# schematic.net
KiCad netlist of a schematic drawn in EasyEDA
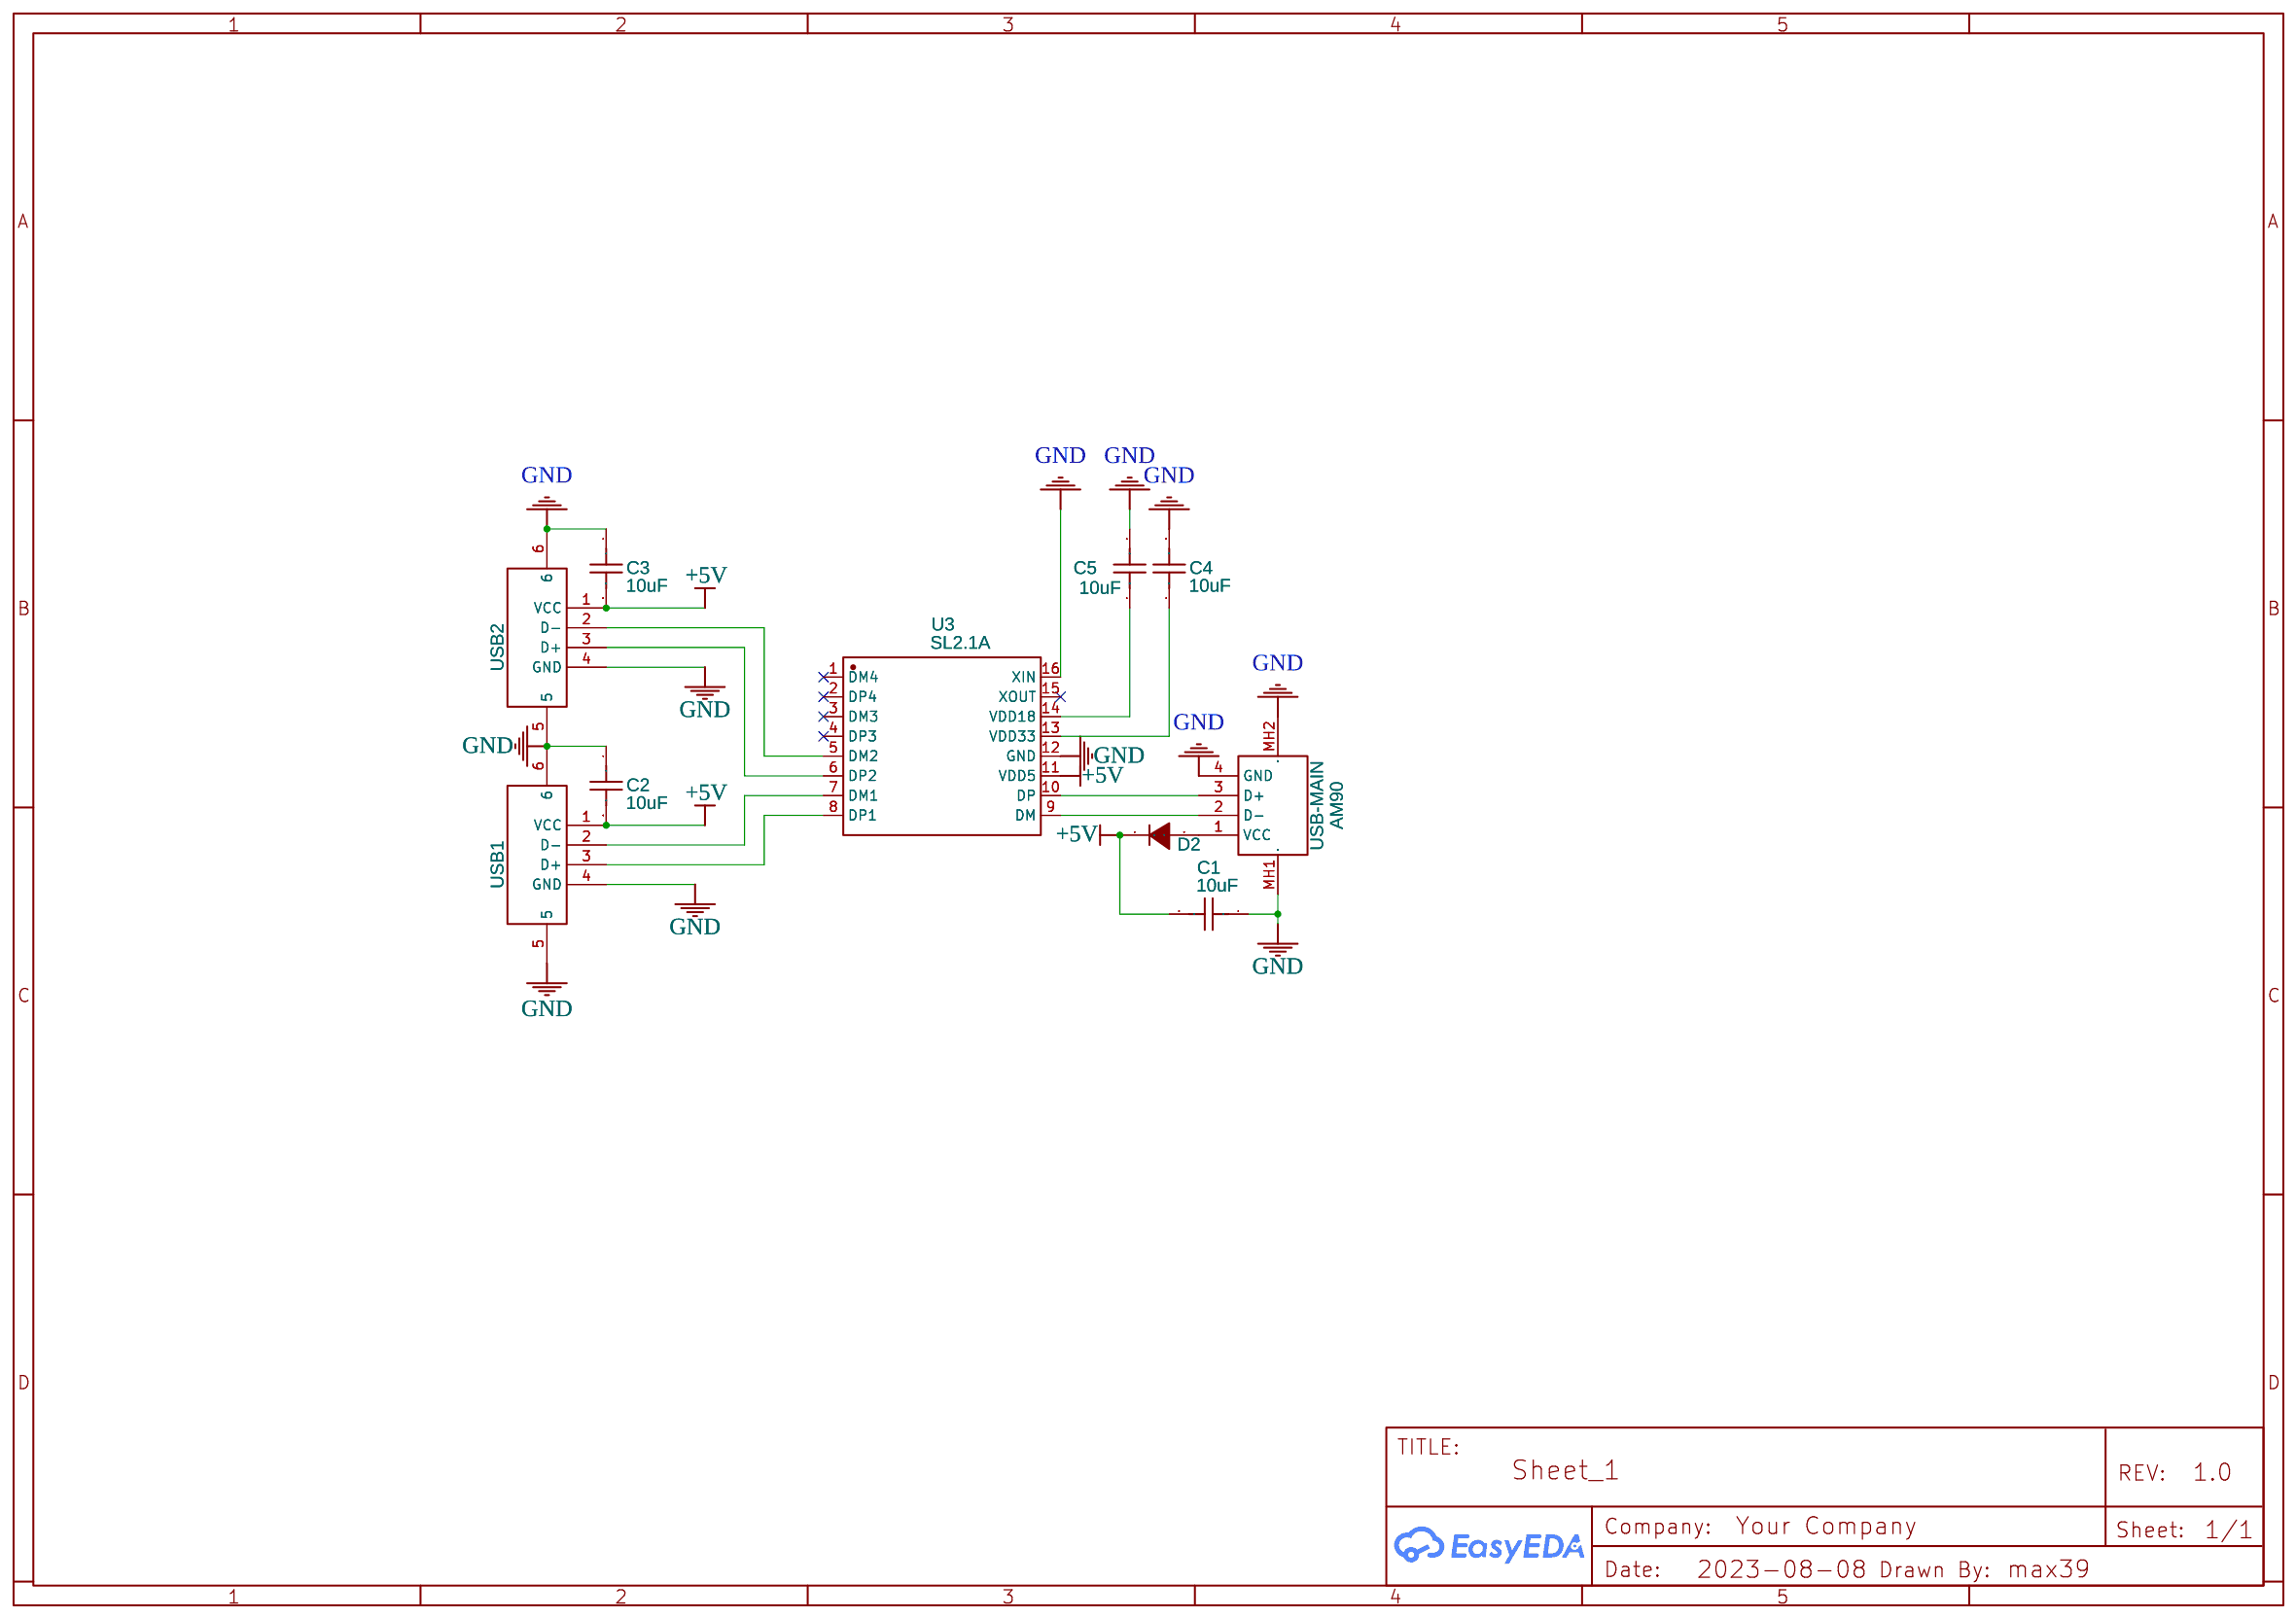
[diagram p0: schematic sheet]

(export (version "E")
  (design (tool "Eeschema 10.0.6"))
  (components
    (comp (ref "C1")
      (value "10uF")
      (fields
        (field (name "Manufacturer Part") "CL10A106KP8NNNC")
        (field (name "Manufacturer") "SAMSUNG(三星)")
      )
      (libsource (lib "") (part "CL10A106KP8NNNC_1"))
    )
    (comp (ref "C2")
      (value "10uF")
      (fields
        (field (name "Manufacturer Part") "CL10A106KP8NNNC")
        (field (name "Manufacturer") "SAMSUNG(三星)")
      )
      (libsource (lib "") (part "CL10A106KP8NNNC"))
    )
    (comp (ref "C3")
      (value "10uF")
      (fields
        (field (name "Manufacturer Part") "CL10A106KP8NNNC")
        (field (name "Manufacturer") "SAMSUNG(三星)")
      )
      (libsource (lib "") (part "CL10A106KP8NNNC"))
    )
    (comp (ref "C4") (value "10uF") (libsource (lib "") (part "C_0603_US")))
    (comp (ref "C5") (value "10uF") (libsource (lib "") (part "C_0603_US")))
    (comp (ref "D2")
      (value "NSR0320MW2T1G")
      (fields (field (name "Manufacturer") "onsemi(安森美)"))
      (libsource (lib "") (part "NSR0320MW2T1G"))
    )
    (comp (ref "U3")
      (value "SL2.1A")
      (fields (field (name "Manufacturer") "CoreChips(和芯润德)"))
      (libsource (lib "") (part "SL2.1A"))
    )
    (comp (ref "USB-MAIN") (value "AM90") (libsource (lib "") (part "AM90")))
    (comp (ref "USB1")
      (value "USB-AF-90-14.4X13.6-H7.0-DIP")
      (fields (field (name "Manufacturer Part") "903-131A1011D10100") (field (name "Manufacturer") "精拓金"))
      (libsource (lib "") (part "USB-AF-90-14.4X13.6-H7.0-DIP"))
    )
    (comp (ref "USB2")
      (value "USB-AF-90-14.4X13.6-H7.0-DIP")
      (fields (field (name "Manufacturer Part") "903-131A1011D10100") (field (name "Manufacturer") "精拓金"))
      (libsource (lib "") (part "USB-AF-90-14.4X13.6-H7.0-DIP"))
    )
  )
  (nets
    (net (code "1") (name "+5V") (class "Default")
      (node (ref "C1") (pin "2") (pinfunction "2_2") (pintype "unspecified"))
      (node (ref "C2") (pin "2") (pinfunction "2_2") (pintype "unspecified"))
      (node (ref "C3") (pin "2") (pinfunction "2_2") (pintype "unspecified"))
      (node (ref "D2") (pin "1") (pinfunction "C_1") (pintype "unspecified"))
      (node (ref "U3") (pin "11") (pinfunction "VDD5_11") (pintype "unspecified"))
      (node (ref "USB1") (pin "1") (pinfunction "VCC_1") (pintype "unspecified"))
      (node (ref "USB2") (pin "1") (pinfunction "VCC_1") (pintype "unspecified"))
    )
    (net (code "2") (name "GND") (class "Default")
      (node (ref "C1") (pin "1") (pinfunction "1_1") (pintype "unspecified"))
      (node (ref "C2") (pin "1") (pinfunction "1_1") (pintype "unspecified"))
      (node (ref "C3") (pin "1") (pinfunction "1_1") (pintype "unspecified"))
      (node (ref "C4") (pin "2") (pinfunction "2_2") (pintype "unspecified"))
      (node (ref "C5") (pin "2") (pinfunction "2_2") (pintype "unspecified"))
      (node (ref "U3") (pin "12") (pinfunction "GND_12") (pintype "unspecified"))
      (node (ref "U3") (pin "16") (pinfunction "XIN_16") (pintype "unspecified"))
      (node (ref "USB-MAIN") (pin "4") (pinfunction "GND_4") (pintype "input"))
      (node (ref "USB-MAIN") (pin "MH1") (pinfunction "MH1_MH1") (pintype "unspecified"))
      (node (ref "USB-MAIN") (pin "MH2") (pinfunction "MH2_MH2") (pintype "unspecified"))
      (node (ref "USB1") (pin "4") (pinfunction "GND_4") (pintype "unspecified"))
      (node (ref "USB1") (pin "5") (pinfunction "5_5") (pintype "unspecified"))
      (node (ref "USB1") (pin "6") (pinfunction "6_6") (pintype "unspecified"))
      (node (ref "USB2") (pin "4") (pinfunction "GND_4") (pintype "unspecified"))
      (node (ref "USB2") (pin "5") (pinfunction "5_5") (pintype "unspecified"))
      (node (ref "USB2") (pin "6") (pinfunction "6_6") (pintype "unspecified"))
    )
    (net (code "3") (name "Net-(D2-A)") (class "Default")
      (node (ref "D2") (pin "2") (pinfunction "A_2") (pintype "unspecified"))
      (node (ref "USB-MAIN") (pin "1") (pinfunction "VCC_1") (pintype "input"))
    )
    (net (code "4") (name "Net-(U3-DM)") (class "Default")
      (node (ref "U3") (pin "9") (pinfunction "DM_9") (pintype "unspecified"))
      (node (ref "USB-MAIN") (pin "2") (pinfunction "D-_2") (pintype "input"))
    )
    (net (code "5") (name "Net-(U3-DM1)") (class "Default")
      (node (ref "U3") (pin "7") (pinfunction "DM1_7") (pintype "unspecified"))
      (node (ref "USB1") (pin "2") (pinfunction "D-_2") (pintype "unspecified"))
    )
    (net (code "6") (name "Net-(U3-DM2)") (class "Default")
      (node (ref "U3") (pin "5") (pinfunction "DM2_5") (pintype "unspecified"))
      (node (ref "USB2") (pin "2") (pinfunction "D-_2") (pintype "unspecified"))
    )
    (net (code "7") (name "Net-(U3-DP)") (class "Default")
      (node (ref "U3") (pin "10") (pinfunction "DP_10") (pintype "unspecified"))
      (node (ref "USB-MAIN") (pin "3") (pinfunction "D+_3") (pintype "input"))
    )
    (net (code "8") (name "Net-(U3-DP1)") (class "Default")
      (node (ref "U3") (pin "8") (pinfunction "DP1_8") (pintype "unspecified"))
      (node (ref "USB1") (pin "3") (pinfunction "D+_3") (pintype "unspecified"))
    )
    (net (code "9") (name "Net-(U3-DP2)") (class "Default")
      (node (ref "U3") (pin "6") (pinfunction "DP2_6") (pintype "unspecified"))
      (node (ref "USB2") (pin "3") (pinfunction "D+_3") (pintype "unspecified"))
    )
    (net (code "10") (name "Net-(U3-VDD18)") (class "Default")
      (node (ref "C5") (pin "1") (pinfunction "1_1") (pintype "unspecified"))
      (node (ref "U3") (pin "14") (pinfunction "VDD18_14") (pintype "unspecified"))
    )
    (net (code "11") (name "Net-(U3-VDD33)") (class "Default")
      (node (ref "C4") (pin "1") (pinfunction "1_1") (pintype "unspecified"))
      (node (ref "U3") (pin "13") (pinfunction "VDD33_13") (pintype "unspecified"))
    )
    (net (code "12") (name "unconnected-(U3-DM3-Pad3)") (class "Default")
      (node (ref "U3") (pin "3") (pinfunction "DM3_3") (pintype "unspecified+no_connect"))
    )
    (net (code "13") (name "unconnected-(U3-DM4-Pad1)") (class "Default")
      (node (ref "U3") (pin "1") (pinfunction "DM4_1") (pintype "unspecified+no_connect"))
    )
    (net (code "14") (name "unconnected-(U3-DP3-Pad4)") (class "Default")
      (node (ref "U3") (pin "4") (pinfunction "DP3_4") (pintype "unspecified+no_connect"))
    )
    (net (code "15") (name "unconnected-(U3-DP4-Pad2)") (class "Default")
      (node (ref "U3") (pin "2") (pinfunction "DP4_2") (pintype "unspecified+no_connect"))
    )
    (net (code "16") (name "unconnected-(U3-XOUT-Pad15)") (class "Default")
      (node (ref "U3") (pin "15") (pinfunction "XOUT_15") (pintype "unspecified+no_connect"))
    )
  )
)
